# 02-ESP32.net
KiCad netlist of a schematic drawn in Altium Designer
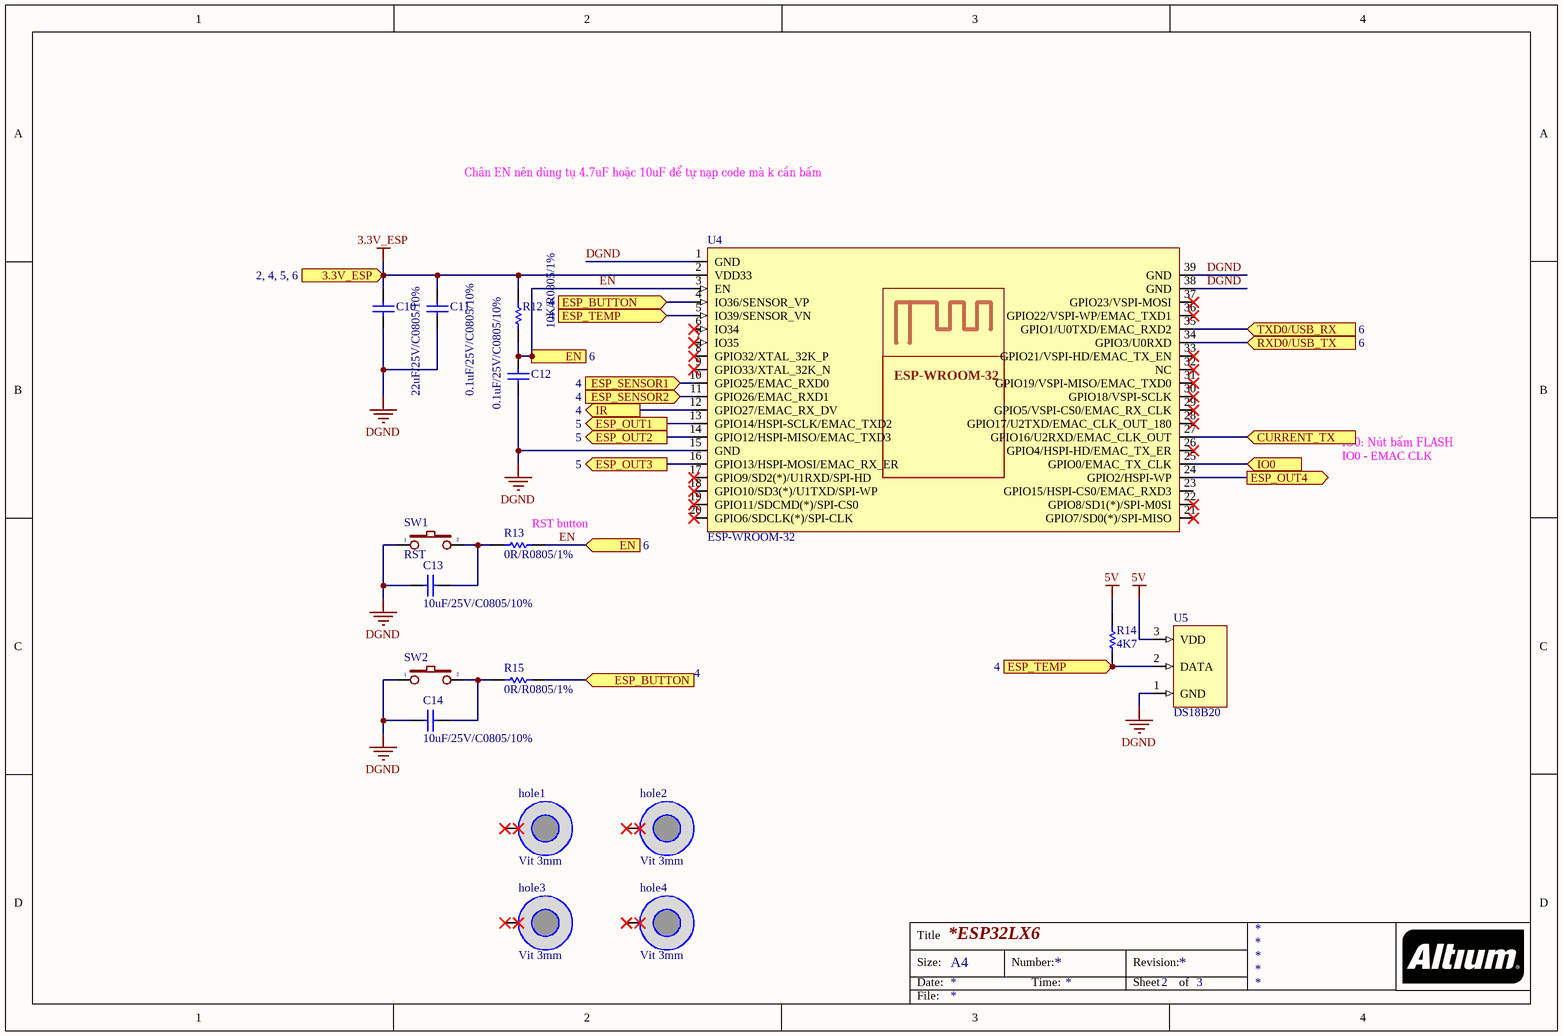
[diagram p0: 02-ESP32.SchDoc]

(export (version "E")
  (design (tool "Eeschema 10.0.6"))
  (components
    (comp (ref "C10")
      (value "22uF/25V/C0805/10%")
      (footprint "CAP_CERA_C2012(CC0805INCH)")
      (description "22µF ±20% 25V Ceramic Capacitor X5R 0805 (2012 Metric)")
      (fields (field (name "MANUFACTURER") "Tariff Applied"))
      (libsource (lib "GSHT_181013") (part "0.1uF/50V/C0603/10%"))
    )
    (comp (ref "C11")
      (value "0.1uF/25V/C0805/10%")
      (footprint "CAP_CERA_C2012(CC0805INCH)")
      (description "0.1µF ±10% 25V Ceramic Capacitor X7R 0805 (2012 Metric)")
      (libsource (lib "GSHT_181013") (part "0.1uF/50V/C0603/10%"))
    )
    (comp (ref "C12")
      (value "0.1uF/25V/C0805/10%")
      (footprint "CAP_CERA_C2012(CC0805INCH)")
      (description "0.1µF ±10% 25V Ceramic Capacitor X7R 0805 (2012 Metric)")
      (libsource (lib "GSHT_181013") (part "0.1uF/50V/C0603/10%"))
    )
    (comp (ref "C13")
      (value "10uF/25V/C0805/10%")
      (footprint "CAP_CERA_C2012(CC0805INCH)")
      (description "0.1µF ±10% 25V Ceramic Capacitor X7R 0805 (2012 Metric)")
      (libsource (lib "GSHT_181013") (part "0.1uF/50V/C0603/10%"))
    )
    (comp (ref "C14")
      (value "10uF/25V/C0805/10%")
      (footprint "CAP_CERA_C2012(CC0805INCH)")
      (description "0.1µF ±10% 25V Ceramic Capacitor X7R 0805 (2012 Metric)")
      (libsource (lib "GSHT_181013") (part "0.1uF/50V/C0603/10%"))
    )
    (comp (ref "hole1") (value "Vit 3mm") (footprint "Screw 3.0") (libsource (lib "lpson") (part "Vit 3mm")))
    (comp (ref "hole2") (value "Vit 3mm") (footprint "Screw 3.0") (libsource (lib "lpson") (part "Vit 3mm")))
    (comp (ref "hole3") (value "Vit 3mm") (footprint "Screw 3.0") (libsource (lib "lpson") (part "Vit 3mm")))
    (comp (ref "hole4") (value "Vit 3mm") (footprint "Screw 3.0") (libsource (lib "lpson") (part "Vit 3mm")))
    (comp (ref "R12")
      (value "10K/R0805/1%")
      (footprint "Res 0805 SMD")
      (description "10 kOhms ±1% 0.125W, 1/8W Chip Resistor 0805 (2012 Metric) Thick Film")
      (libsource (lib "GSHT_181013") (part "200K/R0603/1%"))
    )
    (comp (ref "R13")
      (value "0R/R0805/1%")
      (footprint "Res 0805 SMD")
      (description "0 Ohms Jumper 0.125W, 1/8W Chip Resistor 0805 (2012 Metric) Automotive AEC-Q200 Thick Film")
      (libsource (lib "GSHT_181013") (part "200K/R0603/1%"))
    )
    (comp (ref "R14")
      (value "4K7")
      (footprint "Res 0805 SMD")
      (description "4k7 Ohms Jumper 0.125W, 1/8W Chip Resistor 0805 (2012 Metric)")
      (libsource (lib "GSHT_181013") (part "200K/R0603/1%"))
    )
    (comp (ref "R15")
      (value "0R/R0805/1%")
      (footprint "Res 0805 SMD")
      (description "0 Ohms Jumper 0.125W, 1/8W Chip Resistor 0805 (2012 Metric) Automotive AEC-Q200 Thick Film")
      (libsource (lib "GSHT_181013") (part "200K/R0603/1%"))
    )
    (comp (ref "SW1")
      (value "RST")
      (footprint "Button 3x4mm")
      (description "SWITCH TACTILE SPST-NO 0.05A 12V")
      (libsource (lib "lpson") (part "SW2"))
    )
    (comp (ref "SW2")
      (value "RST")
      (footprint "Button 3x4mm")
      (description "SWITCH TACTILE SPST-NO 0.05A 12V")
      (libsource (lib "lpson") (part "SW2"))
    )
    (comp (ref "U4")
      (value "ESP-WROOM-32")
      (footprint "ESP32 WROOM")
      (description "ESP-WROOM-32 (8MB), WIFI MODULE 64 MBITS SPI FLASH")
      (libsource (lib "lpson") (part "ESP-WROOM-32"))
    )
    (comp (ref "U5") (value "DS18B20") (libsource (lib "Schlib1") (part "DS18B20")))
  )
  (nets
    (net (code "1") (name "/CURRENT_TX") (class "Default")
      (node (ref "U4") (pin "27") (pinfunction "GPIO16/U2RXD/EMAC_CLK_OUT_27") (pintype "passive"))
    )
    (net (code "2") (name "/EN") (class "Default")
      (node (ref "C12") (pin "2") (pinfunction "2_2") (pintype "passive"))
      (node (ref "R12") (pin "2") (pinfunction "2_2") (pintype "passive"))
      (node (ref "R13") (pin "2") (pinfunction "2_2") (pintype "passive"))
      (node (ref "U4") (pin "3") (pinfunction "EN_3") (pintype "input"))
    )
    (net (code "3") (name "/ESP_BUTTON") (class "Default")
      (node (ref "R15") (pin "2") (pinfunction "2_2") (pintype "passive"))
      (node (ref "U4") (pin "4") (pinfunction "IO36/SENSOR_VP_4") (pintype "input"))
    )
    (net (code "4") (name "/ESP_OUT1") (class "Default")
      (node (ref "U4") (pin "13") (pinfunction "GPIO14/HSPI-SCLK/EMAC_TXD2_13") (pintype "passive"))
    )
    (net (code "5") (name "/ESP_OUT2") (class "Default")
      (node (ref "U4") (pin "14") (pinfunction "GPIO12/HSPI-MISO/EMAC_TXD3_14") (pintype "passive"))
    )
    (net (code "6") (name "/ESP_OUT3") (class "Default")
      (node (ref "U4") (pin "16") (pinfunction "GPIO13/HSPI-MOSI/EMAC_RX_ER_16") (pintype "passive"))
    )
    (net (code "7") (name "/ESP_OUT4") (class "Default")
      (node (ref "U4") (pin "24") (pinfunction "GPIO2/HSPI-WP_24") (pintype "passive"))
    )
    (net (code "8") (name "/ESP_SENSOR1") (class "Default")
      (node (ref "U4") (pin "10") (pinfunction "GPIO25/EMAC_RXD0_10") (pintype "passive"))
    )
    (net (code "9") (name "/ESP_SENSOR2") (class "Default")
      (node (ref "U4") (pin "11") (pinfunction "GPIO26/EMAC_RXD1_11") (pintype "passive"))
    )
    (net (code "10") (name "/ESP_TEMP") (class "Default")
      (node (ref "R14") (pin "1") (pinfunction "1_1") (pintype "passive"))
      (node (ref "U4") (pin "5") (pinfunction "IO39/SENSOR_VN_5") (pintype "input"))
      (node (ref "U5") (pin "2") (pinfunction "DATA_2") (pintype "input"))
    )
    (net (code "11") (name "/IO0") (class "Default")
      (node (ref "U4") (pin "25") (pinfunction "GPIO0/EMAC_TX_CLK_25") (pintype "passive"))
    )
    (net (code "12") (name "/IR") (class "Default")
      (node (ref "U4") (pin "12") (pinfunction "GPIO27/EMAC_RX_DV_12") (pintype "passive"))
    )
    (net (code "13") (name "/RXD0{slash}USB_TX") (class "Default")
      (node (ref "U4") (pin "34") (pinfunction "GPIO3/U0RXD_34") (pintype "passive"))
    )
    (net (code "14") (name "/TXD0{slash}USB_RX") (class "Default")
      (node (ref "U4") (pin "35") (pinfunction "GPIO1/U0TXD/EMAC_RXD2_35") (pintype "passive"))
    )
    (net (code "15") (name "3.3V_ESP") (class "Default")
      (node (ref "C10") (pin "2") (pinfunction "2_2") (pintype "passive"))
      (node (ref "C11") (pin "2") (pinfunction "2_2") (pintype "passive"))
      (node (ref "R12") (pin "1") (pinfunction "1_1") (pintype "passive"))
      (node (ref "U4") (pin "2") (pinfunction "VDD33_2") (pintype "passive"))
    )
    (net (code "16") (name "5V") (class "Default")
      (node (ref "R14") (pin "2") (pinfunction "2_2") (pintype "passive"))
      (node (ref "U5") (pin "3") (pinfunction "VDD_3") (pintype "input"))
    )
    (net (code "17") (name "DGND") (class "Default")
      (node (ref "C10") (pin "1") (pinfunction "1_1") (pintype "passive"))
      (node (ref "C11") (pin "1") (pinfunction "1_1") (pintype "passive"))
      (node (ref "C12") (pin "1") (pinfunction "1_1") (pintype "passive"))
      (node (ref "C13") (pin "2") (pinfunction "2_2") (pintype "passive"))
      (node (ref "C14") (pin "2") (pinfunction "2_2") (pintype "passive"))
      (node (ref "SW1") (pin "1") (pinfunction "1_1") (pintype "passive"))
      (node (ref "SW2") (pin "1") (pinfunction "1_1") (pintype "passive"))
      (node (ref "U4") (pin "1") (pinfunction "GND_1") (pintype "passive"))
      (node (ref "U4") (pin "15") (pinfunction "GND_15") (pintype "passive"))
      (node (ref "U4") (pin "38") (pinfunction "GND_38") (pintype "passive"))
      (node (ref "U4") (pin "39") (pinfunction "GND_39") (pintype "passive"))
      (node (ref "U5") (pin "1") (pinfunction "GND_1") (pintype "input"))
    )
    (net (code "18") (name "Net-(C13-Pad1)") (class "Default")
      (node (ref "C13") (pin "1") (pinfunction "1_1") (pintype "passive"))
      (node (ref "R13") (pin "1") (pinfunction "1_1") (pintype "passive"))
      (node (ref "SW1") (pin "2") (pinfunction "2_2") (pintype "passive"))
    )
    (net (code "19") (name "Net-(C14-Pad1)") (class "Default")
      (node (ref "C14") (pin "1") (pinfunction "1_1") (pintype "passive"))
      (node (ref "R15") (pin "1") (pinfunction "1_1") (pintype "passive"))
      (node (ref "SW2") (pin "2") (pinfunction "2_2") (pintype "passive"))
    )
    (net (code "20") (name "unconnected-(U4-GPIO4{slash}HSPI-HD{slash}EMAC_TX_ER-Pad26)") (class "Default")
      (node (ref "U4") (pin "26") (pinfunction "GPIO4/HSPI-HD/EMAC_TX_ER_26") (pintype "passive+no_connect"))
    )
    (net (code "21") (name "unconnected-(U4-GPIO5{slash}VSPI-CS0{slash}EMAC_RX_CLK-Pad29)") (class "Default")
      (node (ref "U4") (pin "29") (pinfunction "GPIO5/VSPI-CS0/EMAC_RX_CLK_29") (pintype "passive+no_connect"))
    )
    (net (code "22") (name "unconnected-(U4-GPIO6{slash}SDCLK(*){slash}SPI-CLK-Pad20)") (class "Default")
      (node (ref "U4") (pin "20") (pinfunction "GPIO6/SDCLK(*)/SPI-CLK_20") (pintype "passive+no_connect"))
    )
    (net (code "23") (name "unconnected-(U4-GPIO7{slash}SD0(*){slash}SPI-MISO-Pad21)") (class "Default")
      (node (ref "U4") (pin "21") (pinfunction "GPIO7/SD0(*)/SPI-MISO_21") (pintype "passive+no_connect"))
    )
    (net (code "24") (name "unconnected-(U4-GPIO8{slash}SD1(*){slash}SPI-M0SI-Pad22)") (class "Default")
      (node (ref "U4") (pin "22") (pinfunction "GPIO8/SD1(*)/SPI-M0SI_22") (pintype "passive+no_connect"))
    )
    (net (code "25") (name "unconnected-(U4-GPIO9{slash}SD2(*){slash}U1RXD{slash}SPI-HD-Pad17)") (class "Default")
      (node (ref "U4") (pin "17") (pinfunction "GPIO9/SD2(*)/U1RXD/SPI-HD_17") (pintype "passive+no_connect"))
    )
    (net (code "26") (name "unconnected-(U4-GPIO10{slash}SD3(*){slash}U1TXD{slash}SPI-WP-Pad18)") (class "Default")
      (node (ref "U4") (pin "18") (pinfunction "GPIO10/SD3(*)/U1TXD/SPI-WP_18") (pintype "passive+no_connect"))
    )
    (net (code "27") (name "unconnected-(U4-GPIO11{slash}SDCMD(*){slash}SPI-CS0-Pad19)") (class "Default")
      (node (ref "U4") (pin "19") (pinfunction "GPIO11/SDCMD(*)/SPI-CS0_19") (pintype "passive+no_connect"))
    )
    (net (code "28") (name "unconnected-(U4-GPIO15{slash}HSPI-CS0{slash}EMAC_RXD3-Pad23)") (class "Default")
      (node (ref "U4") (pin "23") (pinfunction "GPIO15/HSPI-CS0/EMAC_RXD3_23") (pintype "passive"))
    )
    (net (code "29") (name "unconnected-(U4-GPIO17{slash}U2TXD{slash}EMAC_CLK_OUT_180-Pad28)") (class "Default")
      (node (ref "U4") (pin "28") (pinfunction "GPIO17/U2TXD/EMAC_CLK_OUT_180_28") (pintype "passive+no_connect"))
    )
    (net (code "30") (name "unconnected-(U4-GPIO18{slash}VSPI-SCLK-Pad30)") (class "Default")
      (node (ref "U4") (pin "30") (pinfunction "GPIO18/VSPI-SCLK_30") (pintype "passive+no_connect"))
    )
    (net (code "31") (name "unconnected-(U4-GPIO19{slash}VSPI-MISO{slash}EMAC_TXD0-Pad31)") (class "Default")
      (node (ref "U4") (pin "31") (pinfunction "GPIO19/VSPI-MISO/EMAC_TXD0_31") (pintype "passive+no_connect"))
    )
    (net (code "32") (name "unconnected-(U4-GPIO21{slash}VSPI-HD{slash}EMAC_TX_EN-Pad33)") (class "Default")
      (node (ref "U4") (pin "33") (pinfunction "GPIO21/VSPI-HD/EMAC_TX_EN_33") (pintype "passive+no_connect"))
    )
    (net (code "33") (name "unconnected-(U4-GPIO22{slash}VSPI-WP{slash}EMAC_TXD1-Pad36)") (class "Default")
      (node (ref "U4") (pin "36") (pinfunction "GPIO22/VSPI-WP/EMAC_TXD1_36") (pintype "passive+no_connect"))
    )
    (net (code "34") (name "unconnected-(U4-GPIO23{slash}VSPI-MOSI-Pad37)") (class "Default")
      (node (ref "U4") (pin "37") (pinfunction "GPIO23/VSPI-MOSI_37") (pintype "passive+no_connect"))
    )
    (net (code "35") (name "unconnected-(U4-GPIO32{slash}XTAL_32K_P-Pad8)") (class "Default")
      (node (ref "U4") (pin "8") (pinfunction "GPIO32/XTAL_32K_P_8") (pintype "passive+no_connect"))
    )
    (net (code "36") (name "unconnected-(U4-GPIO33{slash}XTAL_32K_N-Pad9)") (class "Default")
      (node (ref "U4") (pin "9") (pinfunction "GPIO33/XTAL_32K_N_9") (pintype "passive+no_connect"))
    )
    (net (code "37") (name "unconnected-(U4-IO34-Pad6)") (class "Default")
      (node (ref "U4") (pin "6") (pinfunction "IO34_6") (pintype "input+no_connect"))
    )
    (net (code "38") (name "unconnected-(U4-IO35-Pad7)") (class "Default")
      (node (ref "U4") (pin "7") (pinfunction "IO35_7") (pintype "input+no_connect"))
    )
    (net (code "39") (name "unconnected-(U4-NC-Pad32)") (class "Default")
      (node (ref "U4") (pin "32") (pinfunction "NC_32") (pintype "passive+no_connect"))
    )
    (net (code "40") (name "unconnected-(hole1-hole-Pad1)") (class "Default")
      (node (ref "hole1") (pin "1") (pinfunction "hole_1") (pintype "passive+no_connect"))
    )
    (net (code "41") (name "unconnected-(hole2-hole-Pad1)") (class "Default")
      (node (ref "hole2") (pin "1") (pinfunction "hole_1") (pintype "passive+no_connect"))
    )
    (net (code "42") (name "unconnected-(hole3-hole-Pad1)") (class "Default")
      (node (ref "hole3") (pin "1") (pinfunction "hole_1") (pintype "passive+no_connect"))
    )
    (net (code "43") (name "unconnected-(hole4-hole-Pad1)") (class "Default")
      (node (ref "hole4") (pin "1") (pinfunction "hole_1") (pintype "passive+no_connect"))
    )
  )
)
